# Power_Supply.net
KiCad netlist of a schematic drawn in Altium Designer
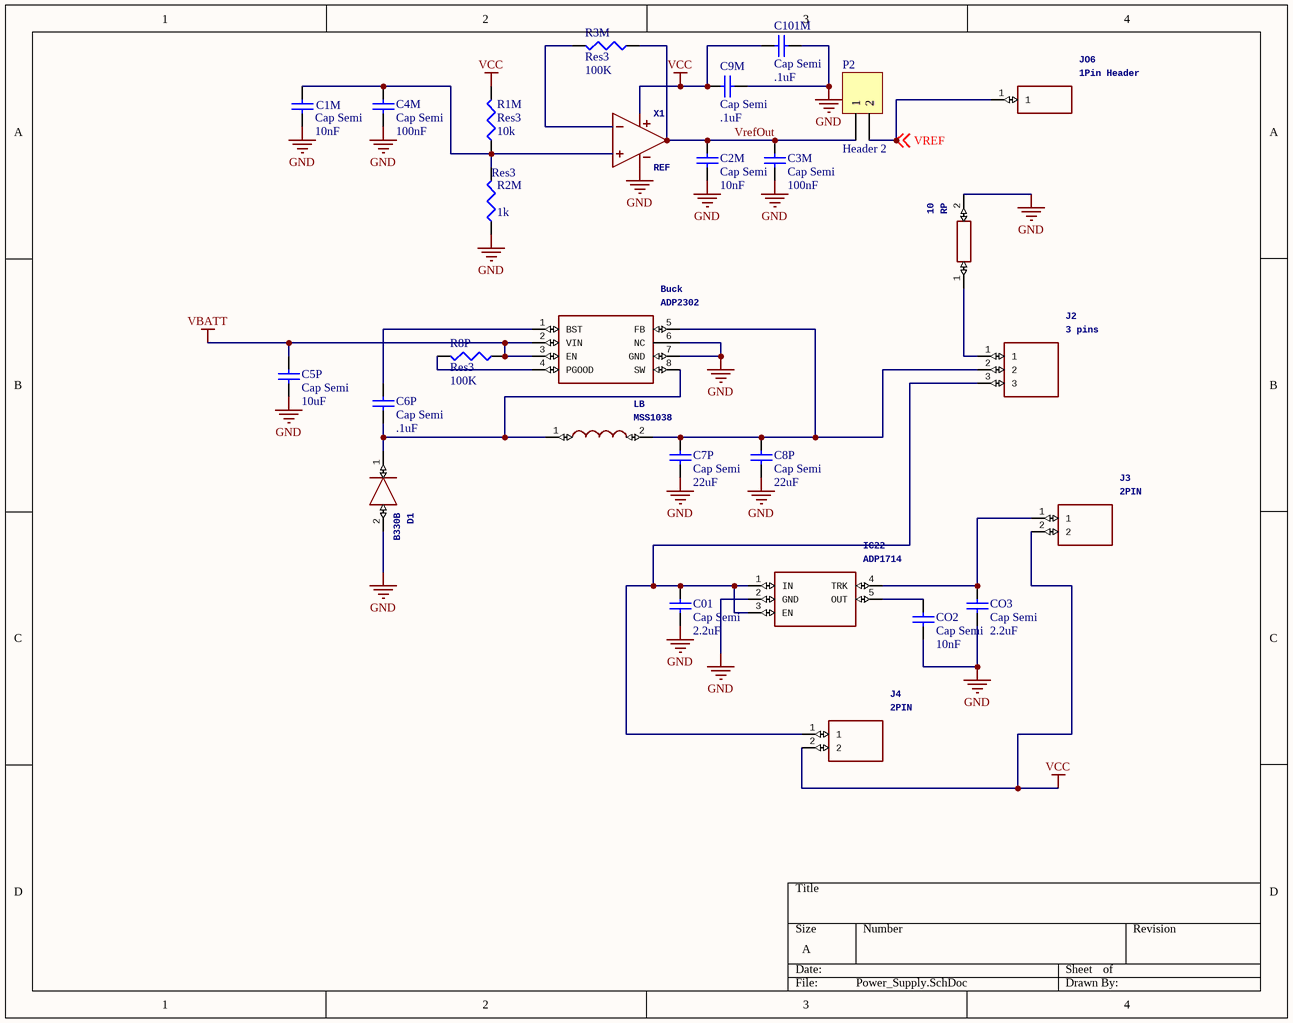
[diagram p0: Power_Supply.SchDoc]

(export (version "E")
  (design (tool "Eeschema 10.0.6"))
  (components
    (comp (ref "10")
      (value "RP")
      (footprint "RESAD3800W75L1600D550")
      (fields
        (field (name "MANUFACTURER_PART_NUMBER") "ROX3SJ220R")
        (field (name "RS_PART_NUMBER") "1615998")
      )
      (libsource (lib "ROX3SJ220R") (part "ROX3SJ220R"))
    )
    (comp (ref "Buck")
      (value "ADP2302")
      (footprint "SOIC127P600X175-9N")
      (fields
        (field (name "MANUFACTURER_PART_NUMBER") "ADP2302ARDZ-5.0-R7")
        (field (name "RS_PART_NUMBER") "7591815P")
      )
      (libsource (lib "ADP2302ARDZ-5") (part "ADP2302ARDZ-5.0-R7"))
    )
    (comp (ref "C01")
      (value "Cap Semi")
      (footprint "1608[0603]")
      (description "Capacitor (Semiconductor SIM Model)")
      (fields (field (name "ALTIUM_VALUE") "2.2uF") (field (name "PUBLISHER") "Altium Limited"))
      (libsource (lib "Miscellaneous Devices") (part "Cap Semi"))
    )
    (comp (ref "C1M")
      (value "Cap Semi")
      (footprint "CAPPM6032X280N")
      (description "Capacitor (Semiconductor SIM Model)")
      (fields (field (name "ALTIUM_VALUE") "10nF") (field (name "PUBLISHER") "Altium Limited"))
      (libsource (lib "Miscellaneous Devices") (part "Cap Semi"))
    )
    (comp (ref "C2M")
      (value "Cap Semi")
      (footprint "CAPPM6032X280N")
      (description "Capacitor (Semiconductor SIM Model)")
      (fields (field (name "ALTIUM_VALUE") "10nF") (field (name "PUBLISHER") "Altium Limited"))
      (libsource (lib "Miscellaneous Devices") (part "Cap Semi"))
    )
    (comp (ref "C3M")
      (value "Cap Semi")
      (footprint "1608[0603]")
      (description "Capacitor (Semiconductor SIM Model)")
      (fields (field (name "ALTIUM_VALUE") "100nF") (field (name "PUBLISHER") "Altium Limited"))
      (libsource (lib "Miscellaneous Devices") (part "Cap Semi"))
    )
    (comp (ref "C4M")
      (value "Cap Semi")
      (footprint "1608[0603]")
      (description "Capacitor (Semiconductor SIM Model)")
      (fields (field (name "ALTIUM_VALUE") "100nF") (field (name "PUBLISHER") "Altium Limited"))
      (libsource (lib "Miscellaneous Devices") (part "Cap Semi"))
    )
    (comp (ref "C5P")
      (value "Cap Semi")
      (footprint "1608[0603]")
      (description "Capacitor (Semiconductor SIM Model)")
      (fields (field (name "ALTIUM_VALUE") "10uF") (field (name "PUBLISHER") "Altium Limited"))
      (libsource (lib "Miscellaneous Devices") (part "Cap Semi"))
    )
    (comp (ref "C6P")
      (value "Cap Semi")
      (footprint "1608[0603]")
      (description "Capacitor (Semiconductor SIM Model)")
      (fields (field (name "ALTIUM_VALUE") ".1uF") (field (name "PUBLISHER") "Altium Limited"))
      (libsource (lib "Miscellaneous Devices") (part "Cap Semi"))
    )
    (comp (ref "C7P")
      (value "Cap Semi")
      (footprint "1608[0603]")
      (description "Capacitor (Semiconductor SIM Model)")
      (fields (field (name "ALTIUM_VALUE") "22uF") (field (name "PUBLISHER") "Altium Limited"))
      (libsource (lib "Miscellaneous Devices") (part "Cap Semi"))
    )
    (comp (ref "C8P")
      (value "Cap Semi")
      (footprint "1608[0603]")
      (description "Capacitor (Semiconductor SIM Model)")
      (fields (field (name "ALTIUM_VALUE") "22uF") (field (name "PUBLISHER") "Altium Limited"))
      (libsource (lib "Miscellaneous Devices") (part "Cap Semi"))
    )
    (comp (ref "C9M")
      (value "Cap Semi")
      (footprint "1608[0603]")
      (description "Capacitor (Semiconductor SIM Model)")
      (fields (field (name "ALTIUM_VALUE") ".1uF") (field (name "PUBLISHER") "Altium Limited"))
      (libsource (lib "Miscellaneous Devices") (part "Cap Semi"))
    )
    (comp (ref "C101M")
      (value "Cap Semi")
      (footprint "CAPPM6032X280N")
      (description "Capacitor (Semiconductor SIM Model)")
      (fields (field (name "ALTIUM_VALUE") ".1uF") (field (name "PUBLISHER") "Altium Limited"))
      (libsource (lib "Miscellaneous Devices") (part "Cap Semi"))
    )
    (comp (ref "CO2")
      (value "Cap Semi")
      (footprint "1608[0603]")
      (description "Capacitor (Semiconductor SIM Model)")
      (fields (field (name "ALTIUM_VALUE") "10nF") (field (name "PUBLISHER") "Altium Limited"))
      (libsource (lib "Miscellaneous Devices") (part "Cap Semi"))
    )
    (comp (ref "CO3")
      (value "Cap Semi")
      (footprint "1608[0603]")
      (description "Capacitor (Semiconductor SIM Model)")
      (fields (field (name "ALTIUM_VALUE") "2.2uF") (field (name "PUBLISHER") "Altium Limited"))
      (libsource (lib "Miscellaneous Devices") (part "Cap Semi"))
    )
    (comp (ref "D1")
      (value "B330B")
      (footprint "DIOM5336X250N")
      (fields
        (field (name "MANUFACTURER_PART_NUMBER") "B330B-13-F")
        (field (name "RS_PART_NUMBER") "9228339")
      )
      (libsource (lib "B330B-13-F") (part "B330B-13-F"))
    )
    (comp (ref "IC22")
      (value "ADP1714")
      (footprint "SOT95P280X100-5N")
      (fields (field (name "MANUFACTURER_PART_NUMBER") "ADP1714AUJZ-3.3-R7"))
      (libsource (lib "ADP1714AUJZ-3") (part "ADP1714AUJZ-3.3-R7"))
    )
    (comp (ref "J2")
      (value "3 pins")
      (footprint "HDRV3W95P0X254_1X3_762X254X869")
      (fields
        (field (name "MANUFACTURER_PART_NUMBER") "61300311121")
        (field (name "RS_PART_NUMBER") "1725145")
      )
      (libsource (lib "61300311121") (part "61300311121"))
    )
    (comp (ref "J3")
      (value "2PIN")
      (footprint "HDRV2W110P0X254_1X2_508X254X85")
      (fields
        (field (name "MANUFACTURER_PART_NUMBER") "61300211121")
        (field (name "RS_PART_NUMBER") "8281581P")
      )
      (libsource (lib "61300211121") (part "61300211121"))
    )
    (comp (ref "J4")
      (value "2PIN")
      (footprint "HDRV2W110P0X254_1X2_508X254X85")
      (fields
        (field (name "MANUFACTURER_PART_NUMBER") "61300211121")
        (field (name "RS_PART_NUMBER") "8281581P")
      )
      (libsource (lib "61300211121") (part "61300211121"))
    )
    (comp (ref "JO6")
      (value "1Pin Header")
      (footprint "68000-401HLF")
      (fields
        (field (name "MANUFACTURER_PART_NUMBER") "68000-401HLF")
        (field (name "RS_PART_NUMBER") "8632706")
      )
      (libsource (lib "68000-401HLF") (part "68000-401HLF"))
    )
    (comp (ref "LB")
      (value "MSS1038")
      (footprint "INDM102102X400N")
      (fields (field (name "MANUFACTURER_PART_NUMBER") "MSS1038-183MLB"))
      (libsource (lib "MSS1038-183MLB") (part "MSS1038-183MLB"))
    )
    (comp (ref "P2")
      (value "Header 2")
      (footprint "HDRV2W110P0X254_1X2_508X254X85")
      (description "Header, 2-Pin")
      (fields (field (name "PUBLISHER") "Altium Limited"))
      (libsource (lib "Miscellaneous Connectors") (part "Header 2"))
    )
    (comp (ref "R1M")
      (value "Res3")
      (footprint "1608[0603]")
      (description "Resistor")
      (fields (field (name "ALTIUM_VALUE") "10k") (field (name "PUBLISHER") "Altium Limited"))
      (libsource (lib "Miscellaneous Devices") (part "Res3"))
    )
    (comp (ref "R2M")
      (value "Res3")
      (footprint "1608[0603]")
      (description "Resistor")
      (fields (field (name "ALTIUM_VALUE") "1k") (field (name "PUBLISHER") "Altium Limited"))
      (libsource (lib "Miscellaneous Devices") (part "Res3"))
    )
    (comp (ref "R3M")
      (value "Res3")
      (footprint "1608[0603]")
      (description "Resistor")
      (fields (field (name "ALTIUM_VALUE") "100K") (field (name "PUBLISHER") "Altium Limited"))
      (libsource (lib "Miscellaneous Devices") (part "Res3"))
    )
    (comp (ref "R8P")
      (value "Res3")
      (footprint "1608[0603]")
      (description "Resistor")
      (fields (field (name "ALTIUM_VALUE") "100K") (field (name "PUBLISHER") "Altium Limited"))
      (libsource (lib "Miscellaneous Devices") (part "Res3"))
    )
    (comp (ref "X1")
      (value "REF")
      (footprint "SOT95P290X145-5N")
      (fields (field (name "LIBRARYNAME") "Opamps"))
      (libsource (lib "Opamps") (part "OPAMP2"))
    )
  )
  (nets
    (net (code "1") (name "/VrefOut") (class "Default")
      (node (ref "C2M") (pin "2") (pinfunction "2_2") (pintype "passive"))
      (node (ref "C3M") (pin "2") (pinfunction "2_2") (pintype "passive"))
      (node (ref "P2") (pin "1") (pinfunction "1_1") (pintype "passive"))
      (node (ref "R3M") (pin "2") (pinfunction "2_2") (pintype "passive"))
      (node (ref "X1") (pin "1") (pinfunction "OUT_1") (pintype "passive"))
    )
    (net (code "2") (name "GND") (class "Default")
      (node (ref "10") (pin "2") (pinfunction "2_2") (pintype "bidirectional"))
      (node (ref "Buck") (pin "6") (pinfunction "NC_6") (pintype "passive"))
      (node (ref "Buck") (pin "7") (pinfunction "GND_7") (pintype "bidirectional"))
      (node (ref "C01") (pin "1") (pinfunction "1_1") (pintype "passive"))
      (node (ref "C101M") (pin "1") (pinfunction "1_1") (pintype "passive"))
      (node (ref "C1M") (pin "1") (pinfunction "1_1") (pintype "passive"))
      (node (ref "C2M") (pin "1") (pinfunction "1_1") (pintype "passive"))
      (node (ref "C3M") (pin "1") (pinfunction "1_1") (pintype "passive"))
      (node (ref "C4M") (pin "1") (pinfunction "1_1") (pintype "passive"))
      (node (ref "C5P") (pin "1") (pinfunction "1_1") (pintype "passive"))
      (node (ref "C7P") (pin "1") (pinfunction "1_1") (pintype "passive"))
      (node (ref "C8P") (pin "1") (pinfunction "1_1") (pintype "passive"))
      (node (ref "C9M") (pin "1") (pinfunction "1_1") (pintype "passive"))
      (node (ref "CO2") (pin "1") (pinfunction "1_1") (pintype "passive"))
      (node (ref "CO3") (pin "1") (pinfunction "1_1") (pintype "passive"))
      (node (ref "D1") (pin "2") (pinfunction "A_2") (pintype "bidirectional"))
      (node (ref "IC22") (pin "2") (pinfunction "GND_2") (pintype "bidirectional"))
      (node (ref "R2M") (pin "2") (pinfunction "2_2") (pintype "passive"))
      (node (ref "X1") (pin "2") (pinfunction "V-_2") (pintype "passive"))
    )
    (net (code "3") (name "Net-(10-Pad1)") (class "Default")
      (node (ref "10") (pin "1") (pinfunction "1_1") (pintype "bidirectional"))
      (node (ref "J2") (pin "1") (pinfunction "1_1") (pintype "bidirectional"))
    )
    (net (code "4") (name "Net-(Buck-BST)") (class "Default")
      (node (ref "Buck") (pin "1") (pinfunction "BST_1") (pintype "bidirectional"))
      (node (ref "C6P") (pin "2") (pinfunction "2_2") (pintype "passive"))
    )
    (net (code "5") (name "Net-(Buck-FB)") (class "Default")
      (node (ref "Buck") (pin "5") (pinfunction "FB_5") (pintype "bidirectional"))
      (node (ref "C7P") (pin "2") (pinfunction "2_2") (pintype "passive"))
      (node (ref "C8P") (pin "2") (pinfunction "2_2") (pintype "passive"))
      (node (ref "J2") (pin "2") (pinfunction "2_2") (pintype "bidirectional"))
      (node (ref "LB") (pin "2") (pinfunction "2_2") (pintype "bidirectional"))
    )
    (net (code "6") (name "Net-(Buck-PGOOD)") (class "Default")
      (node (ref "Buck") (pin "4") (pinfunction "PGOOD_4") (pintype "bidirectional"))
      (node (ref "R8P") (pin "1") (pinfunction "1_1") (pintype "passive"))
    )
    (net (code "7") (name "Net-(Buck-SW)") (class "Default")
      (node (ref "Buck") (pin "8") (pinfunction "SW_8") (pintype "bidirectional"))
      (node (ref "C6P") (pin "1") (pinfunction "1_1") (pintype "passive"))
      (node (ref "D1") (pin "1") (pinfunction "K_1") (pintype "bidirectional"))
      (node (ref "LB") (pin "1") (pinfunction "1_1") (pintype "bidirectional"))
    )
    (net (code "8") (name "Net-(IC22-EN)") (class "Default")
      (node (ref "C01") (pin "2") (pinfunction "2_2") (pintype "passive"))
      (node (ref "IC22") (pin "1") (pinfunction "IN_1") (pintype "bidirectional"))
      (node (ref "IC22") (pin "3") (pinfunction "EN_3") (pintype "bidirectional"))
      (node (ref "J2") (pin "3") (pinfunction "3_3") (pintype "bidirectional"))
      (node (ref "J4") (pin "1") (pinfunction "1_1") (pintype "bidirectional"))
    )
    (net (code "9") (name "Net-(IC22-OUT)") (class "Default")
      (node (ref "CO2") (pin "2") (pinfunction "2_2") (pintype "passive"))
      (node (ref "IC22") (pin "5") (pinfunction "OUT_5") (pintype "bidirectional"))
    )
    (net (code "10") (name "Net-(IC22-TRK)") (class "Default")
      (node (ref "CO3") (pin "2") (pinfunction "2_2") (pintype "passive"))
      (node (ref "IC22") (pin "4") (pinfunction "TRK_4") (pintype "bidirectional"))
      (node (ref "J3") (pin "1") (pinfunction "1_1") (pintype "bidirectional"))
    )
    (net (code "11") (name "Net-(X1-IN+)") (class "Default")
      (node (ref "C1M") (pin "2") (pinfunction "2_2") (pintype "passive"))
      (node (ref "C4M") (pin "2") (pinfunction "2_2") (pintype "passive"))
      (node (ref "R1M") (pin "2") (pinfunction "2_2") (pintype "passive"))
      (node (ref "R2M") (pin "1") (pinfunction "1_1") (pintype "passive"))
      (node (ref "X1") (pin "3") (pinfunction "IN+_3") (pintype "passive"))
    )
    (net (code "12") (name "Net-(X1-IN-)") (class "Default")
      (node (ref "R3M") (pin "1") (pinfunction "1_1") (pintype "passive"))
      (node (ref "X1") (pin "4") (pinfunction "IN-_4") (pintype "passive"))
    )
    (net (code "13") (name "VBATT") (class "Default")
      (node (ref "Buck") (pin "2") (pinfunction "VIN_2") (pintype "bidirectional"))
      (node (ref "Buck") (pin "3") (pinfunction "EN_3") (pintype "bidirectional"))
      (node (ref "C5P") (pin "2") (pinfunction "2_2") (pintype "passive"))
      (node (ref "R8P") (pin "2") (pinfunction "2_2") (pintype "passive"))
    )
    (net (code "14") (name "VCC") (class "Default")
      (node (ref "C101M") (pin "2") (pinfunction "2_2") (pintype "passive"))
      (node (ref "C9M") (pin "2") (pinfunction "2_2") (pintype "passive"))
      (node (ref "J3") (pin "2") (pinfunction "2_2") (pintype "bidirectional"))
      (node (ref "J4") (pin "2") (pinfunction "2_2") (pintype "bidirectional"))
      (node (ref "R1M") (pin "1") (pinfunction "1_1") (pintype "passive"))
      (node (ref "X1") (pin "5") (pinfunction "V+_5") (pintype "passive"))
    )
    (net (code "15") (name "VREF") (class "Default")
      (node (ref "JO6") (pin "1") (pinfunction "1_1") (pintype "bidirectional"))
      (node (ref "P2") (pin "2") (pinfunction "2_2") (pintype "passive"))
    )
  )
)
